# Flight_Controller_V1_0.net
KiCad netlist of a schematic drawn in EAGLE
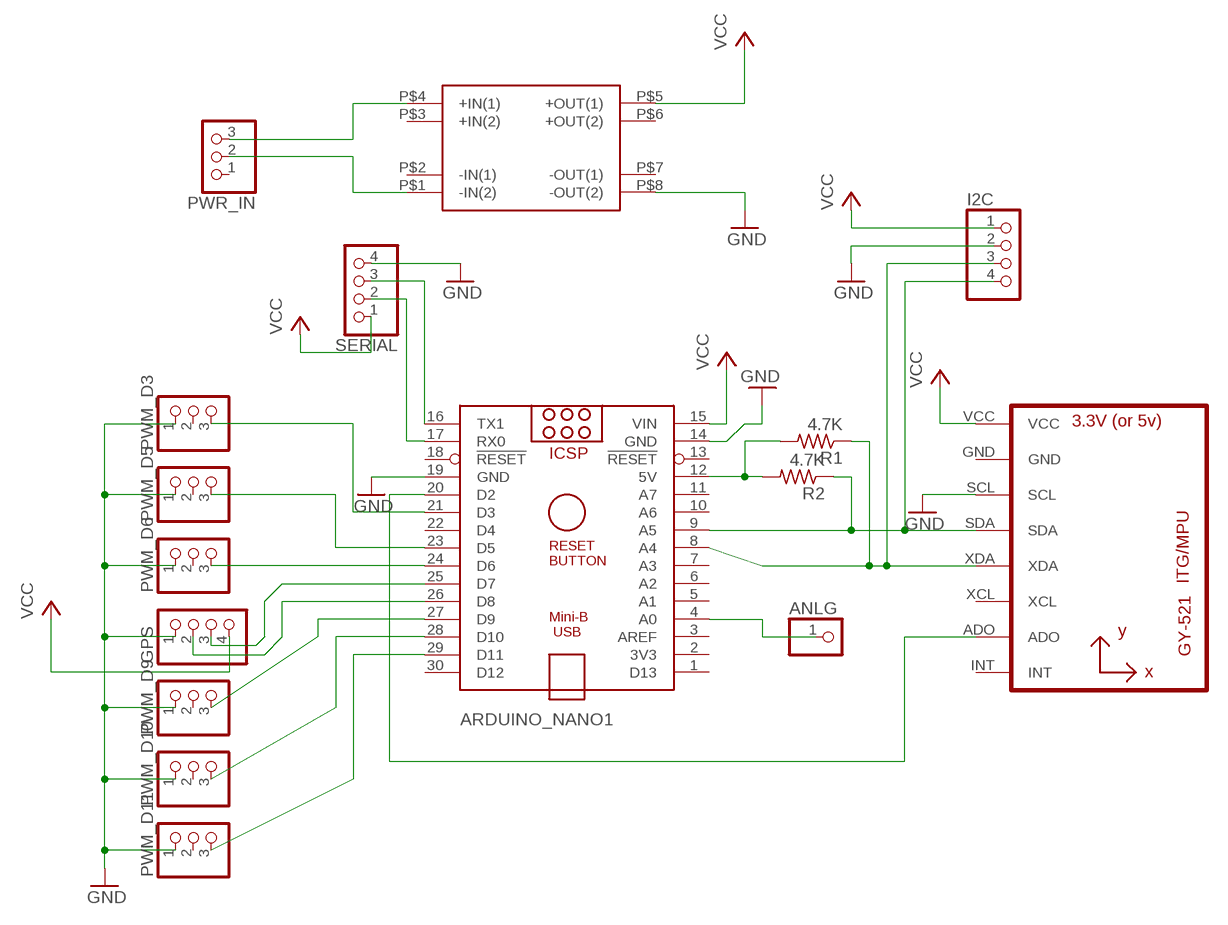
[diagram p0: schematic, sheet 1]

(export (version "E")
  (design (tool "Eeschema 10.0.6"))
  (components
    (comp (ref "ANLG")
      (value "PINHD-1X1")
      (footprint "eagle-import:1X01")
      (libsource (lib "eagle-import") (part "PINHD-1X1"))
    )
    (comp (ref "ARDUINO_NANO1")
      (value "ARDUINO_NANO")
      (footprint "eagle-import:ARDUINO_NANO")
      (libsource (lib "eagle-import") (part "ARDUINO_NANO"))
    )
    (comp (ref "GPS")
      (value "PINHD-1X4")
      (footprint "eagle-import:1X04")
      (libsource (lib "eagle-import") (part "PINHD-1X4"))
    )
    (comp (ref "I2C")
      (value "PINHD-1X4")
      (footprint "eagle-import:1X04")
      (libsource (lib "eagle-import") (part "PINHD-1X4"))
    )
    (comp (ref "PWM_D3")
      (value "PINHD-1X3")
      (footprint "eagle-import:1X03")
      (libsource (lib "eagle-import") (part "PINHD-1X3"))
    )
    (comp (ref "PWM_D5")
      (value "PINHD-1X3")
      (footprint "eagle-import:1X03")
      (libsource (lib "eagle-import") (part "PINHD-1X3"))
    )
    (comp (ref "PWM_D6")
      (value "PINHD-1X3")
      (footprint "eagle-import:1X03")
      (libsource (lib "eagle-import") (part "PINHD-1X3"))
    )
    (comp (ref "PWM_D9")
      (value "PINHD-1X3")
      (footprint "eagle-import:1X03")
      (libsource (lib "eagle-import") (part "PINHD-1X3"))
    )
    (comp (ref "PWM_D10")
      (value "PINHD-1X3")
      (footprint "eagle-import:1X03")
      (libsource (lib "eagle-import") (part "PINHD-1X3"))
    )
    (comp (ref "PWM_D11")
      (value "PINHD-1X3")
      (footprint "eagle-import:1X03")
      (libsource (lib "eagle-import") (part "PINHD-1X3"))
    )
    (comp (ref "PWR_IN")
      (value "PINHD-1X3")
      (footprint "eagle-import:1X03")
      (libsource (lib "eagle-import") (part "PINHD-1X3"))
    )
    (comp (ref "R1")
      (value "4.7K")
      (footprint "eagle-import:R1206")
      (libsource (lib "eagle-import") (part "R-US_R1206"))
    )
    (comp (ref "R2")
      (value "4.7K")
      (footprint "eagle-import:R1206")
      (libsource (lib "eagle-import") (part "R-US_R1206"))
    )
    (comp (ref "SERIAL")
      (value "PINHD-1X4")
      (footprint "eagle-import:1X04")
      (libsource (lib "eagle-import") (part "PINHD-1X4"))
    )
    (comp (ref "U$1")
      (value "MP1584_DEVICETHROUGH_HOLE")
      (footprint "eagle-import:MP1584_PACKAGE")
      (libsource (lib "eagle-import") (part "MP1584_DEVICETHROUGH_HOLE"))
    )
    (comp (ref "U1")
      (value "GY-521MPU6050")
      (footprint "eagle-import:GY-521")
      (libsource (lib "eagle-import") (part "GY-521MPU6050"))
    )
  )
  (nets
    (net (code "1") (name "GND") (class "Default")
      (node (ref "ARDUINO_NANO1") (pin "14") (pinfunction "GND_14") (pintype "power_in"))
      (node (ref "ARDUINO_NANO1") (pin "19") (pinfunction "GND_19") (pintype "power_in"))
      (node (ref "GPS") (pin "1") (pinfunction "1_1") (pintype "passive"))
      (node (ref "I2C") (pin "2") (pinfunction "2_2") (pintype "passive"))
      (node (ref "PWM_D10") (pin "1") (pinfunction "1_1") (pintype "passive"))
      (node (ref "PWM_D11") (pin "1") (pinfunction "1_1") (pintype "passive"))
      (node (ref "PWM_D3") (pin "1") (pinfunction "1_1") (pintype "passive"))
      (node (ref "PWM_D5") (pin "1") (pinfunction "1_1") (pintype "passive"))
      (node (ref "PWM_D6") (pin "1") (pinfunction "1_1") (pintype "passive"))
      (node (ref "PWM_D9") (pin "1") (pinfunction "1_1") (pintype "passive"))
      (node (ref "SERIAL") (pin "4") (pinfunction "4_4") (pintype "passive"))
      (node (ref "U$1") (pin "P$8") (pinfunction "-OUT(2)_P$8") (pintype "bidirectional"))
      (node (ref "U1") (pin "SCL") (pinfunction "SCL_SCL") (pintype "bidirectional"))
    )
    (net (code "2") (name "Net-(ARDUINO_NANO1-5V)") (class "Default")
      (node (ref "ARDUINO_NANO1") (pin "12") (pinfunction "5V_12") (pintype "power_in"))
      (node (ref "R1") (pin "2") (pinfunction "2_2") (pintype "passive"))
      (node (ref "R2") (pin "2") (pinfunction "2_2") (pintype "passive"))
    )
    (net (code "3") (name "Net-(ARDUINO_NANO1-A0)") (class "Default")
      (node (ref "ANLG") (pin "1") (pinfunction "1_1") (pintype "passive"))
      (node (ref "ARDUINO_NANO1") (pin "4") (pinfunction "A0_4") (pintype "bidirectional"))
    )
    (net (code "4") (name "Net-(ARDUINO_NANO1-A4)") (class "Default")
      (node (ref "ARDUINO_NANO1") (pin "8") (pinfunction "A4_8") (pintype "bidirectional"))
      (node (ref "I2C") (pin "3") (pinfunction "3_3") (pintype "passive"))
      (node (ref "R1") (pin "1") (pinfunction "1_1") (pintype "passive"))
      (node (ref "U1") (pin "XDA") (pinfunction "XDA_XDA") (pintype "bidirectional"))
    )
    (net (code "5") (name "Net-(ARDUINO_NANO1-A5)") (class "Default")
      (node (ref "ARDUINO_NANO1") (pin "9") (pinfunction "A5_9") (pintype "bidirectional"))
      (node (ref "I2C") (pin "4") (pinfunction "4_4") (pintype "passive"))
      (node (ref "R2") (pin "1") (pinfunction "1_1") (pintype "passive"))
      (node (ref "U1") (pin "SDA") (pinfunction "SDA_SDA") (pintype "bidirectional"))
    )
    (net (code "6") (name "Net-(ARDUINO_NANO1-D2)") (class "Default")
      (node (ref "ARDUINO_NANO1") (pin "20") (pinfunction "D2_20") (pintype "bidirectional"))
      (node (ref "U1") (pin "ADO") (pinfunction "ADO_ADO") (pintype "bidirectional"))
    )
    (net (code "7") (name "Net-(ARDUINO_NANO1-D3)") (class "Default")
      (node (ref "ARDUINO_NANO1") (pin "21") (pinfunction "D3_21") (pintype "bidirectional"))
      (node (ref "PWM_D3") (pin "3") (pinfunction "3_3") (pintype "passive"))
    )
    (net (code "8") (name "Net-(ARDUINO_NANO1-D5)") (class "Default")
      (node (ref "ARDUINO_NANO1") (pin "23") (pinfunction "D5_23") (pintype "bidirectional"))
      (node (ref "PWM_D5") (pin "3") (pinfunction "3_3") (pintype "passive"))
    )
    (net (code "9") (name "Net-(ARDUINO_NANO1-D6)") (class "Default")
      (node (ref "ARDUINO_NANO1") (pin "24") (pinfunction "D6_24") (pintype "bidirectional"))
      (node (ref "PWM_D6") (pin "3") (pinfunction "3_3") (pintype "passive"))
    )
    (net (code "10") (name "Net-(ARDUINO_NANO1-D7)") (class "Default")
      (node (ref "ARDUINO_NANO1") (pin "25") (pinfunction "D7_25") (pintype "bidirectional"))
      (node (ref "GPS") (pin "3") (pinfunction "3_3") (pintype "passive"))
    )
    (net (code "11") (name "Net-(ARDUINO_NANO1-D8)") (class "Default")
      (node (ref "ARDUINO_NANO1") (pin "26") (pinfunction "D8_26") (pintype "bidirectional"))
      (node (ref "GPS") (pin "2") (pinfunction "2_2") (pintype "passive"))
    )
    (net (code "12") (name "Net-(ARDUINO_NANO1-D9)") (class "Default")
      (node (ref "ARDUINO_NANO1") (pin "27") (pinfunction "D9_27") (pintype "bidirectional"))
      (node (ref "PWM_D9") (pin "3") (pinfunction "3_3") (pintype "passive"))
    )
    (net (code "13") (name "Net-(ARDUINO_NANO1-D10)") (class "Default")
      (node (ref "ARDUINO_NANO1") (pin "28") (pinfunction "D10_28") (pintype "bidirectional"))
      (node (ref "PWM_D10") (pin "3") (pinfunction "3_3") (pintype "passive"))
    )
    (net (code "14") (name "Net-(ARDUINO_NANO1-D11)") (class "Default")
      (node (ref "ARDUINO_NANO1") (pin "29") (pinfunction "D11_29") (pintype "bidirectional"))
      (node (ref "PWM_D11") (pin "3") (pinfunction "3_3") (pintype "passive"))
    )
    (net (code "15") (name "Net-(ARDUINO_NANO1-RX0)") (class "Default")
      (node (ref "ARDUINO_NANO1") (pin "17") (pinfunction "RX0_17") (pintype "bidirectional"))
      (node (ref "SERIAL") (pin "2") (pinfunction "2_2") (pintype "passive"))
    )
    (net (code "16") (name "Net-(ARDUINO_NANO1-TX1)") (class "Default")
      (node (ref "ARDUINO_NANO1") (pin "16") (pinfunction "TX1_16") (pintype "bidirectional"))
      (node (ref "SERIAL") (pin "3") (pinfunction "3_3") (pintype "passive"))
    )
    (net (code "17") (name "Net-(U$1-+IN(1))") (class "Default")
      (node (ref "PWR_IN") (pin "3") (pinfunction "3_3") (pintype "passive"))
      (node (ref "U$1") (pin "P$4") (pinfunction "+IN(1)_P$4") (pintype "bidirectional"))
    )
    (net (code "18") (name "Net-(U$1--IN(2))") (class "Default")
      (node (ref "PWR_IN") (pin "2") (pinfunction "2_2") (pintype "passive"))
      (node (ref "U$1") (pin "P$1") (pinfunction "-IN(2)_P$1") (pintype "bidirectional"))
    )
    (net (code "19") (name "VCC") (class "Default")
      (node (ref "ARDUINO_NANO1") (pin "15") (pinfunction "VIN_15") (pintype "power_in"))
      (node (ref "GPS") (pin "4") (pinfunction "4_4") (pintype "passive"))
      (node (ref "I2C") (pin "1") (pinfunction "1_1") (pintype "passive"))
      (node (ref "SERIAL") (pin "1") (pinfunction "1_1") (pintype "passive"))
      (node (ref "U$1") (pin "P$5") (pinfunction "+OUT(1)_P$5") (pintype "bidirectional"))
      (node (ref "U1") (pin "VCC") (pinfunction "VCC_VCC") (pintype "bidirectional"))
    )
    (net (code "20") (name "unconnected-(ARDUINO_NANO1-3V3-Pad2)") (class "Default")
      (node (ref "ARDUINO_NANO1") (pin "2") (pinfunction "3V3_2") (pintype "output"))
    )
    (net (code "21") (name "unconnected-(ARDUINO_NANO1-A1-Pad5)") (class "Default")
      (node (ref "ARDUINO_NANO1") (pin "5") (pinfunction "A1_5") (pintype "bidirectional"))
    )
    (net (code "22") (name "unconnected-(ARDUINO_NANO1-A2-Pad6)") (class "Default")
      (node (ref "ARDUINO_NANO1") (pin "6") (pinfunction "A2_6") (pintype "bidirectional"))
    )
    (net (code "23") (name "unconnected-(ARDUINO_NANO1-A3-Pad7)") (class "Default")
      (node (ref "ARDUINO_NANO1") (pin "7") (pinfunction "A3_7") (pintype "bidirectional"))
    )
    (net (code "24") (name "unconnected-(ARDUINO_NANO1-A6-Pad10)") (class "Default")
      (node (ref "ARDUINO_NANO1") (pin "10") (pinfunction "A6_10") (pintype "bidirectional"))
    )
    (net (code "25") (name "unconnected-(ARDUINO_NANO1-A7-Pad11)") (class "Default")
      (node (ref "ARDUINO_NANO1") (pin "11") (pinfunction "A7_11") (pintype "bidirectional"))
    )
    (net (code "26") (name "unconnected-(ARDUINO_NANO1-AREF-Pad3)") (class "Default")
      (node (ref "ARDUINO_NANO1") (pin "3") (pinfunction "AREF_3") (pintype "input"))
    )
    (net (code "27") (name "unconnected-(ARDUINO_NANO1-D4-Pad22)") (class "Default")
      (node (ref "ARDUINO_NANO1") (pin "22") (pinfunction "D4_22") (pintype "bidirectional"))
    )
    (net (code "28") (name "unconnected-(ARDUINO_NANO1-D12-Pad30)") (class "Default")
      (node (ref "ARDUINO_NANO1") (pin "30") (pinfunction "D12_30") (pintype "bidirectional"))
    )
    (net (code "29") (name "unconnected-(ARDUINO_NANO1-D13-Pad1)") (class "Default")
      (node (ref "ARDUINO_NANO1") (pin "1") (pinfunction "D13_1") (pintype "bidirectional"))
    )
    (net (code "30") (name "unconnected-(ARDUINO_NANO1-~{RESET}-Pad13)") (class "Default")
      (node (ref "ARDUINO_NANO1") (pin "13") (pinfunction "~{RESET}_13") (pintype "input"))
    )
    (net (code "31") (name "unconnected-(ARDUINO_NANO1-~{RESET}-Pad18)") (class "Default")
      (node (ref "ARDUINO_NANO1") (pin "18") (pinfunction "~{RESET}_18") (pintype "input"))
    )
    (net (code "32") (name "unconnected-(PWM_D3-Pad2)") (class "Default")
      (node (ref "PWM_D3") (pin "2") (pinfunction "2_2") (pintype "passive"))
    )
    (net (code "33") (name "unconnected-(PWM_D5-Pad2)") (class "Default")
      (node (ref "PWM_D5") (pin "2") (pinfunction "2_2") (pintype "passive"))
    )
    (net (code "34") (name "unconnected-(PWM_D6-Pad2)") (class "Default")
      (node (ref "PWM_D6") (pin "2") (pinfunction "2_2") (pintype "passive"))
    )
    (net (code "35") (name "unconnected-(PWM_D9-Pad2)") (class "Default")
      (node (ref "PWM_D9") (pin "2") (pinfunction "2_2") (pintype "passive"))
    )
    (net (code "36") (name "unconnected-(PWM_D10-Pad2)") (class "Default")
      (node (ref "PWM_D10") (pin "2") (pinfunction "2_2") (pintype "passive"))
    )
    (net (code "37") (name "unconnected-(PWM_D11-Pad2)") (class "Default")
      (node (ref "PWM_D11") (pin "2") (pinfunction "2_2") (pintype "passive"))
    )
    (net (code "38") (name "unconnected-(PWR_IN-Pad1)") (class "Default")
      (node (ref "PWR_IN") (pin "1") (pinfunction "1_1") (pintype "passive"))
    )
    (net (code "39") (name "unconnected-(U$1-+IN(2)-PadP$3)") (class "Default")
      (node (ref "U$1") (pin "P$3") (pinfunction "+IN(2)_P$3") (pintype "bidirectional"))
    )
    (net (code "40") (name "unconnected-(U$1-+OUT(2)-PadP$6)") (class "Default")
      (node (ref "U$1") (pin "P$6") (pinfunction "+OUT(2)_P$6") (pintype "bidirectional"))
    )
    (net (code "41") (name "unconnected-(U$1--IN(1)-PadP$2)") (class "Default")
      (node (ref "U$1") (pin "P$2") (pinfunction "-IN(1)_P$2") (pintype "bidirectional"))
    )
    (net (code "42") (name "unconnected-(U$1--OUT(1)-PadP$7)") (class "Default")
      (node (ref "U$1") (pin "P$7") (pinfunction "-OUT(1)_P$7") (pintype "bidirectional"))
    )
    (net (code "43") (name "unconnected-(U1-PadGND)") (class "Default")
      (node (ref "U1") (pin "GND") (pinfunction "GND_GND") (pintype "bidirectional"))
    )
    (net (code "44") (name "unconnected-(U1-PadINT)") (class "Default")
      (node (ref "U1") (pin "INT") (pinfunction "INT_INT") (pintype "bidirectional"))
    )
    (net (code "45") (name "unconnected-(U1-PadXCL)") (class "Default")
      (node (ref "U1") (pin "XCL") (pinfunction "XCL_XCL") (pintype "bidirectional"))
    )
  )
)
